# Solar_Charger.net
KiCad netlist of a schematic drawn in EAGLE
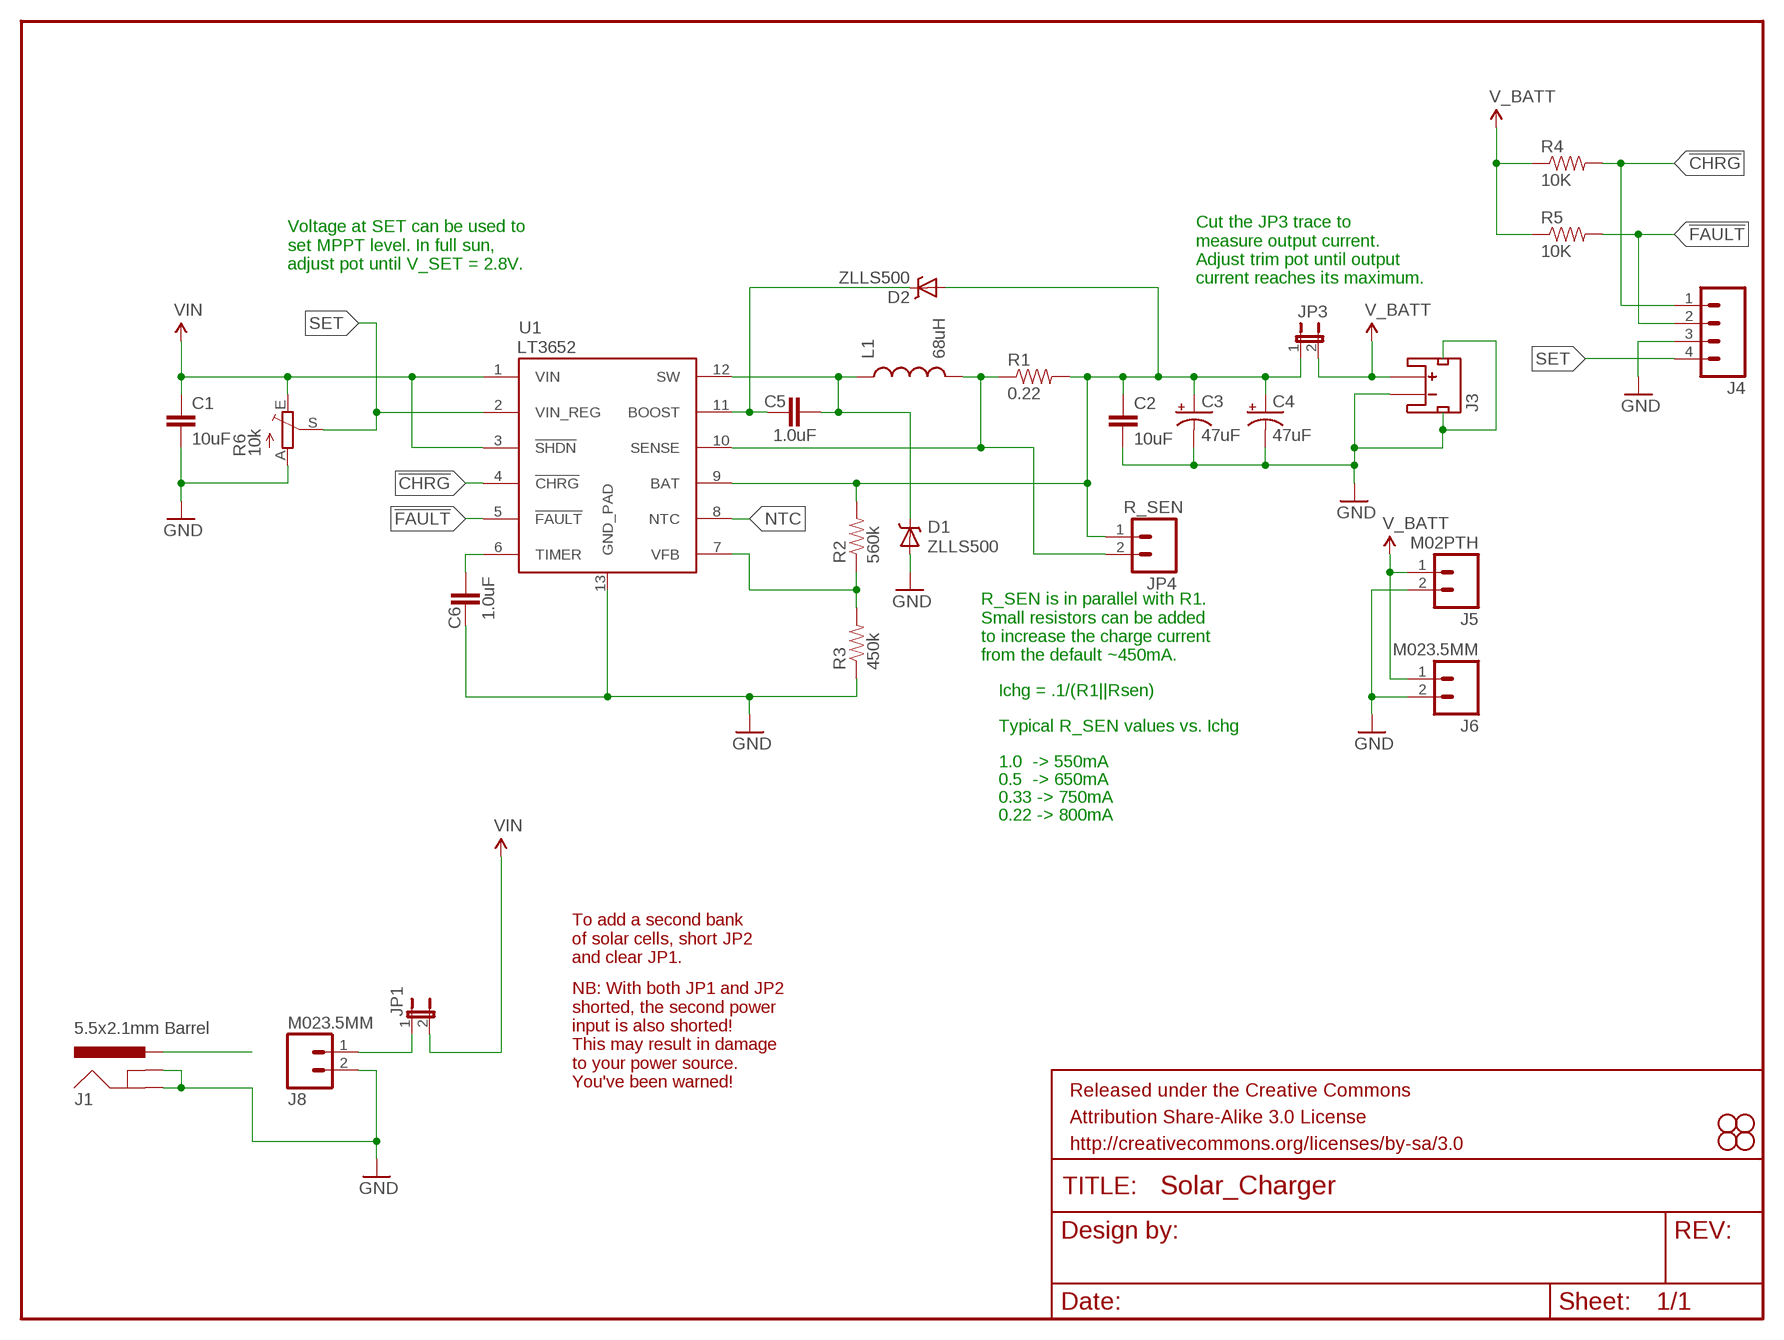
[diagram p0: schematic, sheet 1]

(export (version "E")
  (design (tool "Eeschema 10.0.6"))
  (components
    (comp (ref "C1")
      (value "10uF")
      (footprint "eagle-import:1210")
      (libsource (lib "eagle-import") (part "10UF50V20%(1210)"))
    )
    (comp (ref "C2")
      (value "10uF")
      (footprint "eagle-import:1206")
      (libsource (lib "eagle-import") (part "10UF-6.3V-20%(1206)"))
    )
    (comp (ref "C3")
      (value "47uF")
      (footprint "eagle-import:EIA3528")
      (libsource (lib "eagle-import") (part "47UF-TANT"))
    )
    (comp (ref "C4")
      (value "47uF")
      (footprint "eagle-import:EIA3528")
      (libsource (lib "eagle-import") (part "47UF-TANT"))
    )
    (comp (ref "C5")
      (value "1.0uF")
      (footprint "eagle-import:0603-CAP")
      (libsource (lib "eagle-import") (part "1.0UF-16V-10%(0603)"))
    )
    (comp (ref "C6")
      (value "1.0uF")
      (footprint "eagle-import:0603-CAP")
      (libsource (lib "eagle-import") (part "1.0UF-16V-10%(0603)"))
    )
    (comp (ref "D1")
      (value "ZLLS500")
      (footprint "eagle-import:SOT23")
      (libsource (lib "eagle-import") (part "ZLLS500ZLLS500"))
    )
    (comp (ref "D2")
      (value "ZLLS500")
      (footprint "eagle-import:SOT23")
      (libsource (lib "eagle-import") (part "ZLLS500ZLLS500"))
    )
    (comp (ref "FRAME1")
      (value "FRAME-LETTER")
      (footprint "eagle-import:CREATIVE_COMMONS")
      (libsource (lib "eagle-import") (part "FRAME-LETTER"))
    )
    (comp (ref "J1")
      (value "5.5x2.1mm Barrel")
      (footprint "eagle-import:POWER_JACK_SMD")
      (libsource (lib "eagle-import") (part "POWER_JACKSMD"))
    )
    (comp (ref "J3")
      (value "JST_2MM_MALE")
      (footprint "eagle-import:JST-2-SMD")
      (libsource (lib "eagle-import") (part "JST_2MM_MALE"))
    )
    (comp (ref "J4")
      (value "M04PTH")
      (footprint "eagle-import:1X04")
      (libsource (lib "eagle-import") (part "M04PTH"))
    )
    (comp (ref "J5")
      (value "M02PTH")
      (footprint "eagle-import:1X02")
      (libsource (lib "eagle-import") (part "M02PTH"))
    )
    (comp (ref "J6")
      (value "M023.5MM")
      (footprint "eagle-import:SCREWTERMINAL-3.5MM-2")
      (libsource (lib "eagle-import") (part "M023.5MM"))
    )
    (comp (ref "J8")
      (value "M023.5MM")
      (footprint "eagle-import:SCREWTERMINAL-3.5MM-2")
      (libsource (lib "eagle-import") (part "M023.5MM"))
    )
    (comp (ref "JP1")
      (value "JUMPER-2SMD-NC")
      (footprint "eagle-import:SJ_2S")
      (libsource (lib "eagle-import") (part "JUMPER-2SMD-NC"))
    )
    (comp (ref "JP3")
      (value "JUMPER-PTH-2-NC")
      (footprint "eagle-import:PTH-JUMPER-NC_BOTTOM_NO_SILK")
      (libsource (lib "eagle-import") (part "JUMPER-PTH-2-NC"))
    )
    (comp (ref "JP4")
      (value "R_SEN")
      (footprint "eagle-import:1X02")
      (libsource (lib "eagle-import") (part "M02PTH"))
    )
    (comp (ref "L1")
      (value "68uH")
      (footprint "eagle-import:CR75")
      (libsource (lib "eagle-import") (part "INDUCTOR68UH-1A"))
    )
    (comp (ref "R1")
      (value "0.22")
      (footprint "eagle-import:0805")
      (libsource (lib "eagle-import") (part "0.22OHM1/4W1%(0805)"))
    )
    (comp (ref "R2")
      (value "560k")
      (footprint "eagle-import:0603-RES")
      (libsource (lib "eagle-import") (part "47KOHM1/10W1%(0603)"))
    )
    (comp (ref "R3")
      (value "450k")
      (footprint "eagle-import:0603-RES")
      (libsource (lib "eagle-import") (part "220KOHM1/10W1%(0603)"))
    )
    (comp (ref "R4")
      (value "10K")
      (footprint "eagle-import:0603-RES")
      (libsource (lib "eagle-import") (part "10KOHM1/10W1%(0603)0603"))
    )
    (comp (ref "R5")
      (value "10K")
      (footprint "eagle-import:0603-RES")
      (libsource (lib "eagle-import") (part "10KOHM1/10W1%(0603)0603"))
    )
    (comp (ref "R6")
      (value "10k")
      (footprint "eagle-import:S63S")
      (libsource (lib "eagle-import") (part "TRIM_EU-S63S"))
    )
    (comp (ref "STANDOFF1")
      (value "STAND-OFF")
      (footprint "eagle-import:STAND-OFF")
      (libsource (lib "eagle-import") (part "STAND-OFF"))
    )
    (comp (ref "STANDOFF2")
      (value "STAND-OFF")
      (footprint "eagle-import:STAND-OFF")
      (libsource (lib "eagle-import") (part "STAND-OFF"))
    )
    (comp (ref "STANDOFF3")
      (value "STAND-OFF")
      (footprint "eagle-import:STAND-OFF")
      (libsource (lib "eagle-import") (part "STAND-OFF"))
    )
    (comp (ref "STANDOFF4")
      (value "STAND-OFF")
      (footprint "eagle-import:STAND-OFF")
      (libsource (lib "eagle-import") (part "STAND-OFF"))
    )
    (comp (ref "U1")
      (value "LT3652")
      (footprint "eagle-import:MSOP-12_GND")
      (libsource (lib "eagle-import") (part "LT3652"))
    )
  )
  (nets
    (net (code "1") (name "/~{CHRG}") (class "Default")
      (node (ref "J4") (pin "1") (pinfunction "1_1") (pintype "passive"))
      (node (ref "R4") (pin "2") (pinfunction "2_2") (pintype "passive"))
      (node (ref "U1") (pin "4") (pinfunction "~{CHRG}_4") (pintype "bidirectional"))
    )
    (net (code "2") (name "/~{FAULT}") (class "Default")
      (node (ref "J4") (pin "2") (pinfunction "2_2") (pintype "passive"))
      (node (ref "R5") (pin "2") (pinfunction "2_2") (pintype "passive"))
      (node (ref "U1") (pin "5") (pinfunction "~{FAULT}_5") (pintype "bidirectional"))
    )
    (net (code "3") (name "GND") (class "Default")
      (node (ref "C1") (pin "2") (pinfunction "2_2") (pintype "passive"))
      (node (ref "C2") (pin "2") (pinfunction "2_2") (pintype "passive"))
      (node (ref "C3") (pin "C") (pinfunction "-_C") (pintype "passive"))
      (node (ref "C4") (pin "C") (pinfunction "-_C") (pintype "passive"))
      (node (ref "C6") (pin "1") (pinfunction "1_1") (pintype "passive"))
      (node (ref "D1") (pin "1") (pinfunction "A_1") (pintype "passive"))
      (node (ref "J1") (pin "GND") (pinfunction "GNDBREAK_GND") (pintype "bidirectional"))
      (node (ref "J1") (pin "P$4") (pinfunction "GND_P$4") (pintype "bidirectional"))
      (node (ref "J3") (pin "1") (pinfunction "-_1") (pintype "bidirectional"))
      (node (ref "J3") (pin "NC1") (pinfunction "PAD1_NC1") (pintype "bidirectional"))
      (node (ref "J3") (pin "NC2") (pinfunction "PAD2_NC2") (pintype "bidirectional"))
      (node (ref "J4") (pin "3") (pinfunction "3_3") (pintype "passive"))
      (node (ref "J5") (pin "2") (pinfunction "2_2") (pintype "passive"))
      (node (ref "J6") (pin "2") (pinfunction "2_2") (pintype "passive"))
      (node (ref "J8") (pin "2") (pinfunction "2_2") (pintype "passive"))
      (node (ref "R3") (pin "1") (pinfunction "1_1") (pintype "passive"))
      (node (ref "R6") (pin "A") (pinfunction "A_A") (pintype "passive"))
      (node (ref "U1") (pin "13") (pinfunction "GND_PAD_13") (pintype "bidirectional"))
    )
    (net (code "4") (name "NTC") (class "Default")
      (node (ref "U1") (pin "8") (pinfunction "NTC_8") (pintype "bidirectional"))
    )
    (net (code "5") (name "Net-(C3-+)") (class "Default")
      (node (ref "C2") (pin "1") (pinfunction "1_1") (pintype "passive"))
      (node (ref "C3") (pin "A") (pinfunction "+_A") (pintype "passive"))
      (node (ref "C4") (pin "A") (pinfunction "+_A") (pintype "passive"))
      (node (ref "D2") (pin "1") (pinfunction "A_1") (pintype "passive"))
      (node (ref "JP3") (pin "1") (pinfunction "1_1") (pintype "passive"))
      (node (ref "JP4") (pin "1") (pinfunction "1_1") (pintype "passive"))
      (node (ref "R1") (pin "2") (pinfunction "2_2") (pintype "passive"))
      (node (ref "R2") (pin "2") (pinfunction "2_2") (pintype "passive"))
      (node (ref "U1") (pin "9") (pinfunction "BAT_9") (pintype "bidirectional"))
    )
    (net (code "6") (name "Net-(D1-C)") (class "Default")
      (node (ref "C5") (pin "2") (pinfunction "2_2") (pintype "passive"))
      (node (ref "D1") (pin "3") (pinfunction "C_3") (pintype "passive"))
      (node (ref "L1") (pin "P$1") (pinfunction "1_P$1") (pintype "passive"))
      (node (ref "U1") (pin "12") (pinfunction "SW_12") (pintype "bidirectional"))
    )
    (net (code "7") (name "Net-(D2-C)") (class "Default")
      (node (ref "C5") (pin "1") (pinfunction "1_1") (pintype "passive"))
      (node (ref "D2") (pin "3") (pinfunction "C_3") (pintype "passive"))
      (node (ref "U1") (pin "11") (pinfunction "BOOST_11") (pintype "bidirectional"))
    )
    (net (code "8") (name "Net-(J8-Pad1)") (class "Default")
      (node (ref "J8") (pin "1") (pinfunction "1_1") (pintype "passive"))
      (node (ref "JP1") (pin "1") (pinfunction "1_1") (pintype "passive"))
    )
    (net (code "9") (name "Net-(L1-2)") (class "Default")
      (node (ref "JP4") (pin "2") (pinfunction "2_2") (pintype "passive"))
      (node (ref "L1") (pin "P$2") (pinfunction "2_P$2") (pintype "passive"))
      (node (ref "R1") (pin "1") (pinfunction "1_1") (pintype "passive"))
      (node (ref "U1") (pin "10") (pinfunction "SENSE_10") (pintype "bidirectional"))
    )
    (net (code "10") (name "Net-(U1-TIMER)") (class "Default")
      (node (ref "C6") (pin "2") (pinfunction "2_2") (pintype "passive"))
      (node (ref "U1") (pin "6") (pinfunction "TIMER_6") (pintype "bidirectional"))
    )
    (net (code "11") (name "Net-(U1-VFB)") (class "Default")
      (node (ref "R2") (pin "1") (pinfunction "1_1") (pintype "passive"))
      (node (ref "R3") (pin "2") (pinfunction "2_2") (pintype "passive"))
      (node (ref "U1") (pin "7") (pinfunction "VFB_7") (pintype "bidirectional"))
    )
    (net (code "12") (name "SET") (class "Default")
      (node (ref "J4") (pin "4") (pinfunction "4_4") (pintype "passive"))
      (node (ref "R6") (pin "S") (pinfunction "S_S") (pintype "passive"))
      (node (ref "U1") (pin "2") (pinfunction "VIN_REG_2") (pintype "bidirectional"))
    )
    (net (code "13") (name "VIN") (class "Default")
      (node (ref "C1") (pin "1") (pinfunction "1_1") (pintype "passive"))
      (node (ref "JP1") (pin "2") (pinfunction "2_2") (pintype "passive"))
      (node (ref "R6") (pin "E") (pinfunction "E_E") (pintype "passive"))
      (node (ref "U1") (pin "1") (pinfunction "VIN_1") (pintype "bidirectional"))
      (node (ref "U1") (pin "3") (pinfunction "~{SHDN}_3") (pintype "bidirectional"))
    )
    (net (code "14") (name "V_BATT") (class "Default")
      (node (ref "J3") (pin "2") (pinfunction "+_2") (pintype "bidirectional"))
      (node (ref "J5") (pin "1") (pinfunction "1_1") (pintype "passive"))
      (node (ref "J6") (pin "1") (pinfunction "1_1") (pintype "passive"))
      (node (ref "JP3") (pin "2") (pinfunction "2_2") (pintype "passive"))
      (node (ref "R4") (pin "1") (pinfunction "1_1") (pintype "passive"))
      (node (ref "R5") (pin "1") (pinfunction "1_1") (pintype "passive"))
    )
    (net (code "15") (name "unconnected-(J1-PWR-PadVIN0)") (class "Default")
      (node (ref "J1") (pin "VIN0") (pinfunction "PWR_VIN0") (pintype "bidirectional"))
    )
  )
)
